# PCB-DISP128x32a.net
KiCad netlist of a schematic drawn in EAGLE
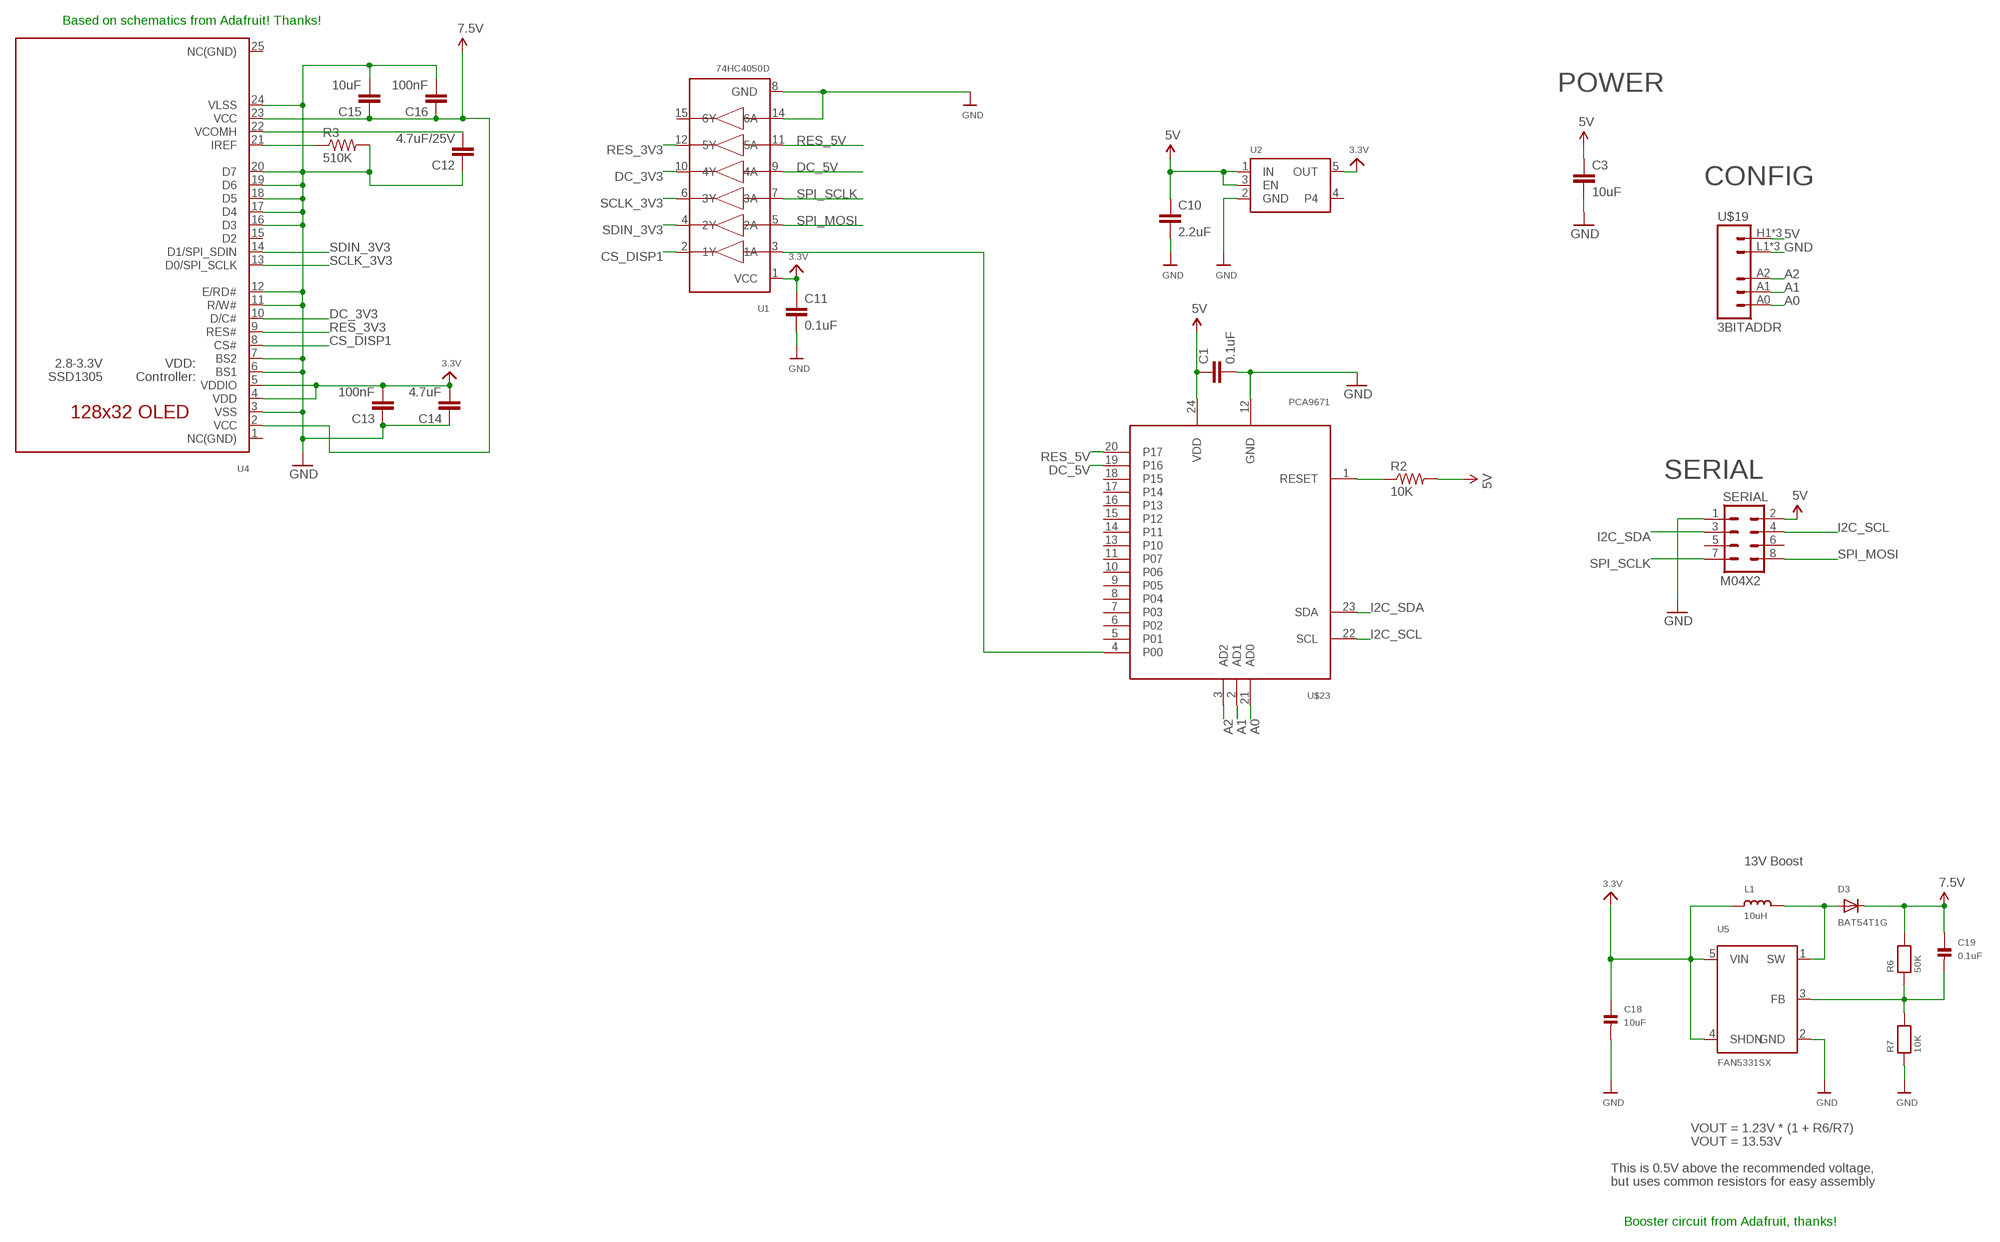
[diagram p0: schematic, sheet 1]

(export (version "E")
  (design (tool "Eeschema 10.0.6"))
  (components
    (comp (ref "C1")
      (value "0.1uF")
      (footprint "eagle-import:0603-CAP")
      (libsource (lib "eagle-import") (part "CAP0603-CAP"))
    )
    (comp (ref "C3")
      (value "10uF")
      (footprint "eagle-import:0805")
      (libsource (lib "eagle-import") (part "CAP0805"))
    )
    (comp (ref "C10")
      (value "2.2uF")
      (footprint "eagle-import:0603-CAP")
      (libsource (lib "eagle-import") (part "CAP0603-CAP"))
    )
    (comp (ref "C11")
      (value "0.1uF")
      (footprint "eagle-import:0603-CAP")
      (libsource (lib "eagle-import") (part "CAP0603-CAP"))
    )
    (comp (ref "C12")
      (value "4.7uF/25V")
      (footprint "eagle-import:0805")
      (libsource (lib "eagle-import") (part "CAP0805"))
    )
    (comp (ref "C13")
      (value "100nF")
      (footprint "eagle-import:0603-CAP")
      (libsource (lib "eagle-import") (part "CAP0603-CAP"))
    )
    (comp (ref "C14")
      (value "4.7uF")
      (footprint "eagle-import:0603-CAP")
      (libsource (lib "eagle-import") (part "CAP0603-CAP"))
    )
    (comp (ref "C15")
      (value "10uF")
      (footprint "eagle-import:0603-CAP")
      (libsource (lib "eagle-import") (part "CAP0603-CAP"))
    )
    (comp (ref "C16")
      (value "100nF")
      (footprint "eagle-import:0603-CAP")
      (libsource (lib "eagle-import") (part "CAP0603-CAP"))
    )
    (comp (ref "C18")
      (value "10uF")
      (footprint "eagle-import:0805")
      (libsource (lib "eagle-import") (part "CAP_CERAMIC0805"))
    )
    (comp (ref "C19")
      (value "0.1uF")
      (footprint "eagle-import:0805")
      (libsource (lib "eagle-import") (part "CAP_CERAMIC0805"))
    )
    (comp (ref "D3")
      (value "BAT54T1G")
      (footprint "eagle-import:SOD-123")
      (libsource (lib "eagle-import") (part "DIODESOD-123"))
    )
    (comp (ref "L1")
      (value "10uH")
      (footprint "eagle-import:INDUCTOR_1007")
      (libsource (lib "eagle-import") (part "INDUCTOR"))
    )
    (comp (ref "R2")
      (value "10K")
      (footprint "eagle-import:0603-RES")
      (libsource (lib "eagle-import") (part "RESISTOR0603-RES"))
    )
    (comp (ref "R3")
      (value "510K")
      (footprint "eagle-import:0603-RES")
      (libsource (lib "eagle-import") (part "RESISTOR0603-RES"))
    )
    (comp (ref "R6")
      (value "50K")
      (footprint "eagle-import:0805")
      (libsource (lib "eagle-import") (part "RESISTOR0805"))
    )
    (comp (ref "R7")
      (value "10K")
      (footprint "eagle-import:0805")
      (libsource (lib "eagle-import") (part "RESISTOR0805"))
    )
    (comp (ref "SERIAL")
      (value "M04X2")
      (footprint "eagle-import:2X4")
      (libsource (lib "eagle-import") (part "M04X2"))
    )
    (comp (ref "U$19")
      (value "3BITADDR")
      (footprint "eagle-import:3BITADDR")
      (libsource (lib "eagle-import") (part "3BITADDR"))
    )
    (comp (ref "U$23")
      (value "PCA9671")
      (footprint "eagle-import:TSSOP24")
      (libsource (lib "eagle-import") (part "PCA9671"))
    )
    (comp (ref "U1")
      (value "74HC4050D")
      (footprint "eagle-import:SOIC16")
      (libsource (lib "eagle-import") (part "74HC4050D"))
    )
    (comp (ref "U2")
      (value "VREG_SOT23-5")
      (footprint "eagle-import:SOT23-5")
      (libsource (lib "eagle-import") (part "VREG_SOT23-5"))
    )
    (comp (ref "U4")
      (value "ER-OLED0.91-2")
      (footprint "eagle-import:ER-OLED0.91-2_WRAPAROUND")
      (libsource (lib "eagle-import") (part "ER-OLED0.91-2"))
    )
    (comp (ref "U5")
      (value "FAN5331SX")
      (footprint "eagle-import:SOT23-5")
      (libsource (lib "eagle-import") (part "FAN5331"))
    )
  )
  (nets
    (net (code "1") (name "3.3V") (class "Default")
      (node (ref "C11") (pin "1") (pinfunction "1_1") (pintype "passive"))
      (node (ref "C13") (pin "2") (pinfunction "2_2") (pintype "passive"))
      (node (ref "C14") (pin "2") (pinfunction "2_2") (pintype "passive"))
      (node (ref "C18") (pin "1") (pinfunction "P$1_1") (pintype "passive"))
      (node (ref "L1") (pin "P$1") (pinfunction "1_P$1") (pintype "passive"))
      (node (ref "U1") (pin "1") (pinfunction "VCC_1") (pintype "bidirectional"))
      (node (ref "U2") (pin "5") (pinfunction "OUT_5") (pintype "bidirectional"))
      (node (ref "U4") (pin "4") (pinfunction "VDD_4") (pintype "power_in"))
      (node (ref "U4") (pin "5") (pinfunction "VDDIO_5") (pintype "power_in"))
      (node (ref "U5") (pin "4") (pinfunction "SHDN_4") (pintype "bidirectional"))
      (node (ref "U5") (pin "5") (pinfunction "VIN_5") (pintype "bidirectional"))
    )
    (net (code "2") (name "5V") (class "Default")
      (node (ref "C1") (pin "1") (pinfunction "1_1") (pintype "passive"))
      (node (ref "C10") (pin "1") (pinfunction "1_1") (pintype "passive"))
      (node (ref "C3") (pin "1") (pinfunction "1_1") (pintype "passive"))
      (node (ref "R2") (pin "2") (pinfunction "2_2") (pintype "passive"))
      (node (ref "SERIAL") (pin "2") (pinfunction "2_2") (pintype "passive"))
      (node (ref "U$19") (pin "H1") (pinfunction "VCC_H1") (pintype "passive"))
      (node (ref "U$19") (pin "H2") (pinfunction "VCC_H2") (pintype "passive"))
      (node (ref "U$19") (pin "H3") (pinfunction "VCC_H3") (pintype "passive"))
      (node (ref "U$23") (pin "24") (pinfunction "VDD_24") (pintype "power_in"))
      (node (ref "U2") (pin "1") (pinfunction "IN_1") (pintype "bidirectional"))
      (node (ref "U2") (pin "3") (pinfunction "EN_3") (pintype "bidirectional"))
    )
    (net (code "3") (name "7.5V") (class "Default")
      (node (ref "C15") (pin "1") (pinfunction "1_1") (pintype "passive"))
      (node (ref "C16") (pin "1") (pinfunction "1_1") (pintype "passive"))
      (node (ref "C19") (pin "1") (pinfunction "P$1_1") (pintype "passive"))
      (node (ref "D3") (pin "C") (pinfunction "C_C") (pintype "passive"))
      (node (ref "R6") (pin "2") (pinfunction "2_2") (pintype "passive"))
      (node (ref "U4") (pin "2") (pinfunction "VCC_2") (pintype "power_in"))
      (node (ref "U4") (pin "23") (pinfunction "VCC_23") (pintype "power_in"))
    )
    (net (code "4") (name "A0") (class "Default")
      (node (ref "U$19") (pin "A0") (pinfunction "A0_A0") (pintype "passive"))
      (node (ref "U$23") (pin "21") (pinfunction "AD0_21") (pintype "input"))
    )
    (net (code "5") (name "A1") (class "Default")
      (node (ref "U$19") (pin "A1") (pinfunction "A1_A1") (pintype "passive"))
      (node (ref "U$23") (pin "2") (pinfunction "AD1_2") (pintype "input"))
    )
    (net (code "6") (name "A2") (class "Default")
      (node (ref "U$19") (pin "A2") (pinfunction "A2_A2") (pintype "passive"))
      (node (ref "U$23") (pin "3") (pinfunction "AD2_3") (pintype "input"))
    )
    (net (code "7") (name "CS_DISP1") (class "Default")
      (node (ref "U1") (pin "2") (pinfunction "1Y_2") (pintype "bidirectional"))
      (node (ref "U4") (pin "8") (pinfunction "CS#_8") (pintype "input"))
    )
    (net (code "8") (name "DC_3V3") (class "Default")
      (node (ref "U1") (pin "10") (pinfunction "4Y_10") (pintype "bidirectional"))
      (node (ref "U4") (pin "10") (pinfunction "D/C#_10") (pintype "input"))
    )
    (net (code "9") (name "DC_5V") (class "Default")
      (node (ref "U$23") (pin "19") (pinfunction "P16_19") (pintype "output"))
      (node (ref "U1") (pin "9") (pinfunction "4A_9") (pintype "bidirectional"))
    )
    (net (code "10") (name "GND") (class "Default")
      (node (ref "C1") (pin "2") (pinfunction "2_2") (pintype "passive"))
      (node (ref "C10") (pin "2") (pinfunction "2_2") (pintype "passive"))
      (node (ref "C11") (pin "2") (pinfunction "2_2") (pintype "passive"))
      (node (ref "C12") (pin "1") (pinfunction "1_1") (pintype "passive"))
      (node (ref "C13") (pin "1") (pinfunction "1_1") (pintype "passive"))
      (node (ref "C14") (pin "1") (pinfunction "1_1") (pintype "passive"))
      (node (ref "C15") (pin "2") (pinfunction "2_2") (pintype "passive"))
      (node (ref "C16") (pin "2") (pinfunction "2_2") (pintype "passive"))
      (node (ref "C18") (pin "2") (pinfunction "P$2_2") (pintype "passive"))
      (node (ref "C3") (pin "2") (pinfunction "2_2") (pintype "passive"))
      (node (ref "R3") (pin "2") (pinfunction "2_2") (pintype "passive"))
      (node (ref "R7") (pin "1") (pinfunction "1_1") (pintype "passive"))
      (node (ref "SERIAL") (pin "1") (pinfunction "1_1") (pintype "passive"))
      (node (ref "U$19") (pin "L1") (pinfunction "GND_L1") (pintype "passive"))
      (node (ref "U$19") (pin "L2") (pinfunction "GND_L2") (pintype "passive"))
      (node (ref "U$19") (pin "L3") (pinfunction "GND_L3") (pintype "passive"))
      (node (ref "U$23") (pin "12") (pinfunction "GND_12") (pintype "power_in"))
      (node (ref "U1") (pin "14") (pinfunction "6A_14") (pintype "bidirectional"))
      (node (ref "U1") (pin "8") (pinfunction "GND_8") (pintype "bidirectional"))
      (node (ref "U2") (pin "2") (pinfunction "GND_2") (pintype "bidirectional"))
      (node (ref "U4") (pin "11") (pinfunction "R/W#_11") (pintype "input"))
      (node (ref "U4") (pin "12") (pinfunction "E/RD#_12") (pintype "input"))
      (node (ref "U4") (pin "16") (pinfunction "D3_16") (pintype "bidirectional"))
      (node (ref "U4") (pin "17") (pinfunction "D4_17") (pintype "bidirectional"))
      (node (ref "U4") (pin "18") (pinfunction "D5_18") (pintype "bidirectional"))
      (node (ref "U4") (pin "19") (pinfunction "D6_19") (pintype "bidirectional"))
      (node (ref "U4") (pin "20") (pinfunction "D7_20") (pintype "bidirectional"))
      (node (ref "U4") (pin "24") (pinfunction "VLSS_24") (pintype "power_in"))
      (node (ref "U4") (pin "3") (pinfunction "VSS_3") (pintype "power_in"))
      (node (ref "U4") (pin "6") (pinfunction "BS1_6") (pintype "input"))
      (node (ref "U4") (pin "7") (pinfunction "BS2_7") (pintype "input"))
      (node (ref "U5") (pin "2") (pinfunction "GND_2") (pintype "bidirectional"))
    )
    (net (code "11") (name "I2C_SCL") (class "Default")
      (node (ref "SERIAL") (pin "4") (pinfunction "4_4") (pintype "passive"))
      (node (ref "U$23") (pin "22") (pinfunction "SCL_22") (pintype "input"))
    )
    (net (code "12") (name "I2C_SDA") (class "Default")
      (node (ref "SERIAL") (pin "3") (pinfunction "3_3") (pintype "passive"))
      (node (ref "U$23") (pin "23") (pinfunction "SDA_23") (pintype "input"))
    )
    (net (code "13") (name "Net-(C19-P$2)") (class "Default")
      (node (ref "C19") (pin "2") (pinfunction "P$2_2") (pintype "passive"))
      (node (ref "R6") (pin "1") (pinfunction "1_1") (pintype "passive"))
      (node (ref "R7") (pin "2") (pinfunction "2_2") (pintype "passive"))
      (node (ref "U5") (pin "3") (pinfunction "FB_3") (pintype "bidirectional"))
    )
    (net (code "14") (name "Net-(L1-2)") (class "Default")
      (node (ref "D3") (pin "A") (pinfunction "A_A") (pintype "passive"))
      (node (ref "L1") (pin "P$2") (pinfunction "2_P$2") (pintype "passive"))
      (node (ref "U5") (pin "1") (pinfunction "SW_1") (pintype "bidirectional"))
    )
    (net (code "15") (name "Net-(U$23-P00)") (class "Default")
      (node (ref "U$23") (pin "4") (pinfunction "P00_4") (pintype "output"))
      (node (ref "U1") (pin "3") (pinfunction "1A_3") (pintype "bidirectional"))
    )
    (net (code "16") (name "Net-(U$23-RESET)") (class "Default")
      (node (ref "R2") (pin "1") (pinfunction "1_1") (pintype "passive"))
      (node (ref "U$23") (pin "1") (pinfunction "RESET_1") (pintype "input"))
    )
    (net (code "17") (name "Net-(U4-IREF)") (class "Default")
      (node (ref "R3") (pin "1") (pinfunction "1_1") (pintype "passive"))
      (node (ref "U4") (pin "21") (pinfunction "IREF_21") (pintype "input"))
    )
    (net (code "18") (name "Net-(U4-VCOMH)") (class "Default")
      (node (ref "C12") (pin "2") (pinfunction "2_2") (pintype "passive"))
      (node (ref "U4") (pin "22") (pinfunction "VCOMH_22") (pintype "output"))
    )
    (net (code "19") (name "RES_3V3") (class "Default")
      (node (ref "U1") (pin "12") (pinfunction "5Y_12") (pintype "bidirectional"))
      (node (ref "U4") (pin "9") (pinfunction "RES#_9") (pintype "input"))
    )
    (net (code "20") (name "RES_5V") (class "Default")
      (node (ref "U$23") (pin "20") (pinfunction "P17_20") (pintype "output"))
      (node (ref "U1") (pin "11") (pinfunction "5A_11") (pintype "bidirectional"))
    )
    (net (code "21") (name "SCLK_3V3") (class "Default")
      (node (ref "U1") (pin "6") (pinfunction "3Y_6") (pintype "bidirectional"))
      (node (ref "U4") (pin "13") (pinfunction "D0/SPI_SCLK_13") (pintype "bidirectional"))
    )
    (net (code "22") (name "SDIN_3V3") (class "Default")
      (node (ref "U1") (pin "4") (pinfunction "2Y_4") (pintype "bidirectional"))
      (node (ref "U4") (pin "14") (pinfunction "D1/SPI_SDIN_14") (pintype "bidirectional"))
    )
    (net (code "23") (name "SPI_MOSI") (class "Default")
      (node (ref "SERIAL") (pin "8") (pinfunction "8_8") (pintype "passive"))
      (node (ref "U1") (pin "5") (pinfunction "2A_5") (pintype "bidirectional"))
    )
    (net (code "24") (name "SPI_SCLK") (class "Default")
      (node (ref "SERIAL") (pin "7") (pinfunction "7_7") (pintype "passive"))
      (node (ref "U1") (pin "7") (pinfunction "3A_7") (pintype "bidirectional"))
    )
    (net (code "25") (name "unconnected-(SERIAL-Pad5)") (class "Default")
      (node (ref "SERIAL") (pin "5") (pinfunction "5_5") (pintype "passive"))
    )
    (net (code "26") (name "unconnected-(SERIAL-Pad6)") (class "Default")
      (node (ref "SERIAL") (pin "6") (pinfunction "6_6") (pintype "passive"))
    )
    (net (code "27") (name "unconnected-(U$23-P01-Pad5)") (class "Default")
      (node (ref "U$23") (pin "5") (pinfunction "P01_5") (pintype "output"))
    )
    (net (code "28") (name "unconnected-(U$23-P02-Pad6)") (class "Default")
      (node (ref "U$23") (pin "6") (pinfunction "P02_6") (pintype "output"))
    )
    (net (code "29") (name "unconnected-(U$23-P03-Pad7)") (class "Default")
      (node (ref "U$23") (pin "7") (pinfunction "P03_7") (pintype "output"))
    )
    (net (code "30") (name "unconnected-(U$23-P04-Pad8)") (class "Default")
      (node (ref "U$23") (pin "8") (pinfunction "P04_8") (pintype "output"))
    )
    (net (code "31") (name "unconnected-(U$23-P05-Pad9)") (class "Default")
      (node (ref "U$23") (pin "9") (pinfunction "P05_9") (pintype "output"))
    )
    (net (code "32") (name "unconnected-(U$23-P06-Pad10)") (class "Default")
      (node (ref "U$23") (pin "10") (pinfunction "P06_10") (pintype "output"))
    )
    (net (code "33") (name "unconnected-(U$23-P07-Pad11)") (class "Default")
      (node (ref "U$23") (pin "11") (pinfunction "P07_11") (pintype "output"))
    )
    (net (code "34") (name "unconnected-(U$23-P10-Pad13)") (class "Default")
      (node (ref "U$23") (pin "13") (pinfunction "P10_13") (pintype "output"))
    )
    (net (code "35") (name "unconnected-(U$23-P11-Pad14)") (class "Default")
      (node (ref "U$23") (pin "14") (pinfunction "P11_14") (pintype "output"))
    )
    (net (code "36") (name "unconnected-(U$23-P12-Pad15)") (class "Default")
      (node (ref "U$23") (pin "15") (pinfunction "P12_15") (pintype "output"))
    )
    (net (code "37") (name "unconnected-(U$23-P13-Pad16)") (class "Default")
      (node (ref "U$23") (pin "16") (pinfunction "P13_16") (pintype "output"))
    )
    (net (code "38") (name "unconnected-(U$23-P14-Pad17)") (class "Default")
      (node (ref "U$23") (pin "17") (pinfunction "P14_17") (pintype "output"))
    )
    (net (code "39") (name "unconnected-(U$23-P15-Pad18)") (class "Default")
      (node (ref "U$23") (pin "18") (pinfunction "P15_18") (pintype "output"))
    )
    (net (code "40") (name "unconnected-(U1-6Y-Pad15)") (class "Default")
      (node (ref "U1") (pin "15") (pinfunction "6Y_15") (pintype "bidirectional"))
    )
    (net (code "41") (name "unconnected-(U2-P4-Pad4)") (class "Default")
      (node (ref "U2") (pin "4") (pinfunction "P4_4") (pintype "bidirectional"))
    )
    (net (code "42") (name "unconnected-(U4-D2-Pad15)") (class "Default")
      (node (ref "U4") (pin "15") (pinfunction "D2_15") (pintype "bidirectional"))
    )
    (net (code "43") (name "unconnected-(U4-NC(GND)-Pad1)") (class "Default")
      (node (ref "U4") (pin "1") (pinfunction "NC(GND)_1") (pintype "input"))
    )
    (net (code "44") (name "unconnected-(U4-NC(GND)-Pad25)") (class "Default")
      (node (ref "U4") (pin "25") (pinfunction "NC(GND)_25") (pintype "input"))
    )
  )
)
